# CHARGING.net
KiCad netlist of a schematic drawn in Altium Designer
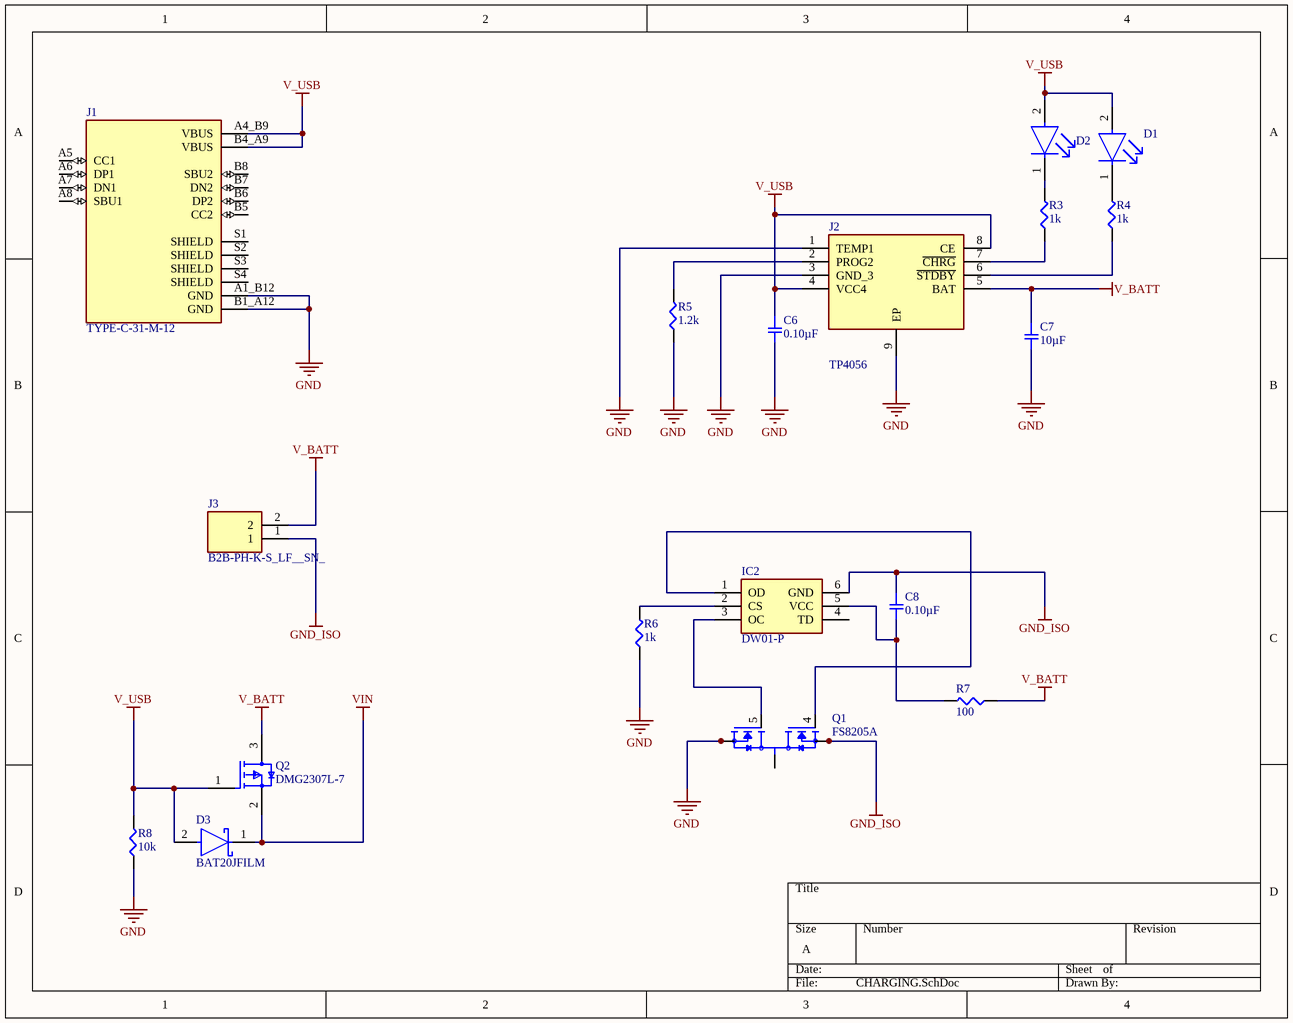
[diagram p0: CHARGING.SchDoc]

(export (version "E")
  (design (tool "Eeschema 10.0.6"))
  (components
    (comp (ref "C6")
      (value "0.10µF")
      (footprint "SMD-0402C")
      (description "CAP CER 0.1UF 16V X7R 0402")
      (fields
        (field (name "DIGI-KEY PART NUMBER") "490-4759-1-ND")
        (field (name "PART NUMBER") "GCM155R71C104KA55D")
      )
      (libsource (lib "capacitor_murata_0402") (part "GCM155R71C104KA55D"))
    )
    (comp (ref "C7")
      (value "10µF")
      (footprint "SMD-0402C")
      (description "CAP CER 10UF 6.3V X5R 0402")
      (fields
        (field (name "DIGI-KEY PART NUMBER") "490-13211-1-ND")
        (field (name "PART NUMBER") "GRJ155R60J106ME11D")
      )
      (libsource (lib "capacitor_murata_0402") (part "GRJ155R60J106ME11D"))
    )
    (comp (ref "C8")
      (value "0.10µF")
      (footprint "SMD-0402C")
      (description "CAP CER 0.1UF 16V X7R 0402")
      (fields
        (field (name "DIGI-KEY PART NUMBER") "490-4759-1-ND")
        (field (name "PART NUMBER") "GCM155R71C104KA55D")
      )
      (libsource (lib "capacitor_murata_0402") (part "GCM155R71C104KA55D"))
    )
    (comp (ref "D1")
      (value "SML-P12VTT86R")
      (footprint "FP-SML-P1-MFG")
      (description "LED RED CLEAR 0402 SMD")
      (fields
        (field (name "OCTOPART") "https://octopart.com/sml-p12vtt86r-rohm-34112315")
        (field (name "MANUFACTURER") "Rohm")
      )
      (libsource (lib "Altium Content Vault") (part "8706943c75ba83719d021d2fdc84c58"))
    )
    (comp (ref "D2")
      (value "APHHS1005CGCK")
      (footprint "FP-APHHS1005CGCK-MFG")
      (description "LED GREEN CLEAR CHIP SMD")
      (libsource (lib "Altium Content Vault") (part "8706943c75ba83719d021d2fdc84c58"))
    )
    (comp (ref "D3")
      (value "BAT20JFILM")
      (footprint "FP-BAT20JFILM-MFG")
      (description "DIODE SCHOTTKY 23V 1A SOD323")
      (libsource (lib "Altium Content Vault") (part "fefb30dabb5d097ae2f038500735429"))
    )
    (comp (ref "IC2")
      (value "DW01-P")
      (footprint "SamacSys:SOT95P280X135-6N")
      (description "Integrated Circuit")
      (libsource (lib "*") (part "DW01-P"))
    )
    (comp (ref "J1")
      (value "TYPE-C-31-M-12")
      (footprint "HRO_TYPE-C-31-M-12")
      (description "USB Connectors 24 Receptacle 1 8.94*7.3mm RoHS")
      (fields (field (name "MF") "HRO Electronics Co., Ltd."))
      (libsource (lib "TYPE-C-31-M-12") (part "TYPE-C-31-M-12"))
    )
    (comp (ref "J2")
      (value "TP4056")
      (footprint "SamacSys:SOIC127P600X175-9N")
      (description "Connector")
      (libsource (lib "SamacSys") (part "TP4056"))
    )
    (comp (ref "J3")
      (value "B2B-PH-K-S_LF__SN_")
      (footprint "SamacSys:SHDR2W50P0X200_1X2_590X450X600P")
      (description "Connector")
      (fields
        (field (name "MANUFACTURER_PART_NUMBER") "B2B-PH-K-S(LF)(SN)")
        (field (name "MOUSER PART NUMBER") "306-B2BPHKSLFSNPP")
      )
      (libsource (lib "*") (part "B2B-PH-K-S_LF__SN_"))
    )
    (comp (ref "Q1")
      (value "FS8205A")
      (footprint "SOP65P640X120-8N")
      (fields (field (name "MF") "Fortune Semiconductor"))
      (libsource (lib "FS8205A (2)") (part "FS8205A"))
    )
    (comp (ref "Q2")
      (value "DMG2307L-7")
      (footprint "FP-SOT23-MFG")
      (description "MOSFET P-CH 30V 2.5A SOT-23")
      (libsource (lib "Altium Content Vault") (part "93d33217dd9b7373daa85f78e0218cc"))
    )
    (comp (ref "R3")
      (value "1k")
      (footprint "SMD-0402-RES")
      (description "RES SMD 1K OHM 5% 1/10W 0402")
      (fields (field (name "PART NUMBER") "ERJ-2GEJ102X") (field (name "DIGI-KEY PART NUMBER") "P1.0KJCT-ND"))
      (libsource (lib "Panasonic_ERJ_0402") (part "ERJ-2GEJ102X"))
    )
    (comp (ref "R4")
      (value "1k")
      (footprint "SMD-0402-RES")
      (description "RES SMD 1K OHM 5% 1/10W 0402")
      (fields (field (name "PART NUMBER") "ERJ-2GEJ102X") (field (name "DIGI-KEY PART NUMBER") "P1.0KJCT-ND"))
      (libsource (lib "Panasonic_ERJ_0402") (part "ERJ-2GEJ102X"))
    )
    (comp (ref "R5")
      (value "1.2k")
      (footprint "SMD-0402-RES")
      (description "RES SMD 1.2K OHM 5% 1/10W 0402")
      (fields (field (name "PART NUMBER") "ERJ-2GEJ122X") (field (name "DIGI-KEY PART NUMBER") "P1.2KJCT-ND"))
      (libsource (lib "Panasonic_ERJ_0402") (part "ERJ-2GEJ122X"))
    )
    (comp (ref "R6")
      (value "1k")
      (footprint "SMD-0402-RES")
      (description "RES SMD 1K OHM 5% 1/10W 0402")
      (fields (field (name "PART NUMBER") "ERJ-2GEJ102X") (field (name "DIGI-KEY PART NUMBER") "P1.0KJCT-ND"))
      (libsource (lib "Panasonic_ERJ_0402") (part "ERJ-2GEJ102X"))
    )
    (comp (ref "R7")
      (value "100")
      (footprint "SMD-0402-RES")
      (description "RES SMD 100 OHM 0.5% 1/16W 0402")
      (fields
        (field (name "PART NUMBER") "ERJ-2RHD1000X")
        (field (name "DIGI-KEY PART NUMBER") "P15983CT-ND")
      )
      (libsource (lib "Panasonic_ERJ_0402") (part "ERJ-2RHD1000X"))
    )
    (comp (ref "R8")
      (value "10k")
      (footprint "SMD-0402-RES")
      (description "RES SMD 10K OHM 5% 1/10W 0402")
      (fields (field (name "PART NUMBER") "ERJ-2GEJ103X") (field (name "DIGI-KEY PART NUMBER") "P10KJCT-ND"))
      (libsource (lib "Panasonic_ERJ_0402") (part "ERJ-2GEJ103X"))
    )
  )
  (nets
    (net (code "1") (name "GND") (class "Default")
      (node (ref "C6") (pin "2") (pinfunction "2_2") (pintype "passive"))
      (node (ref "C7") (pin "2") (pinfunction "2_2") (pintype "passive"))
      (node (ref "J1") (pin "A1_B12") (pinfunction "GND_A1_B12") (pintype "power_in"))
      (node (ref "J1") (pin "B1_A12") (pinfunction "GND_B1_A12") (pintype "power_in"))
      (node (ref "J2") (pin "1") (pinfunction "TEMP1_1") (pintype "passive"))
      (node (ref "J2") (pin "3") (pinfunction "GND_3_3") (pintype "passive"))
      (node (ref "J2") (pin "9") (pinfunction "EP_9") (pintype "passive"))
      (node (ref "Q1") (pin "6") (pinfunction "S2_6") (pintype "passive"))
      (node (ref "Q1") (pin "7") (pinfunction "S2_7") (pintype "passive"))
      (node (ref "R5") (pin "1") (pinfunction "1_1") (pintype "passive"))
      (node (ref "R6") (pin "1") (pinfunction "1_1") (pintype "passive"))
      (node (ref "R8") (pin "1") (pinfunction "1_1") (pintype "passive"))
    )
    (net (code "2") (name "GND_ISO") (class "Default")
      (node (ref "C8") (pin "1") (pinfunction "1_1") (pintype "passive"))
      (node (ref "IC2") (pin "6") (pinfunction "GND_6") (pintype "passive"))
      (node (ref "J3") (pin "1") (pinfunction "1_1") (pintype "passive"))
      (node (ref "Q1") (pin "2") (pinfunction "S1_2") (pintype "passive"))
      (node (ref "Q1") (pin "3") (pinfunction "S1_3") (pintype "passive"))
    )
    (net (code "3") (name "Net-(D1-C)") (class "Default")
      (node (ref "D1") (pin "1") (pinfunction "C_1") (pintype "passive"))
      (node (ref "R4") (pin "2") (pinfunction "2_2") (pintype "passive"))
    )
    (net (code "4") (name "Net-(D2-C)") (class "Default")
      (node (ref "D2") (pin "1") (pinfunction "C_1") (pintype "passive"))
      (node (ref "R3") (pin "2") (pinfunction "2_2") (pintype "passive"))
    )
    (net (code "5") (name "Net-(IC2-CS)") (class "Default")
      (node (ref "IC2") (pin "2") (pinfunction "CS_2") (pintype "passive"))
      (node (ref "R6") (pin "2") (pinfunction "2_2") (pintype "passive"))
    )
    (net (code "6") (name "Net-(IC2-OC)") (class "Default")
      (node (ref "IC2") (pin "3") (pinfunction "OC_3") (pintype "passive"))
      (node (ref "Q1") (pin "5") (pinfunction "G2_5") (pintype "passive"))
    )
    (net (code "7") (name "Net-(IC2-OD)") (class "Default")
      (node (ref "IC2") (pin "1") (pinfunction "OD_1") (pintype "passive"))
      (node (ref "Q1") (pin "4") (pinfunction "G1_4") (pintype "passive"))
    )
    (net (code "8") (name "Net-(IC2-VCC)") (class "Default")
      (node (ref "C8") (pin "2") (pinfunction "2_2") (pintype "passive"))
      (node (ref "IC2") (pin "5") (pinfunction "VCC_5") (pintype "passive"))
      (node (ref "R7") (pin "2") (pinfunction "2_2") (pintype "passive"))
    )
    (net (code "9") (name "Net-(J2-PROG2)") (class "Default")
      (node (ref "J2") (pin "2") (pinfunction "PROG2_2") (pintype "passive"))
      (node (ref "R5") (pin "2") (pinfunction "2_2") (pintype "passive"))
    )
    (net (code "10") (name "Net-(J2-~{CHRG})") (class "Default")
      (node (ref "J2") (pin "7") (pinfunction "~{CHRG}_7") (pintype "passive"))
      (node (ref "R3") (pin "1") (pinfunction "1_1") (pintype "passive"))
    )
    (net (code "11") (name "Net-(J2-~{STDBY})") (class "Default")
      (node (ref "J2") (pin "6") (pinfunction "~{STDBY}_6") (pintype "passive"))
      (node (ref "R4") (pin "1") (pinfunction "1_1") (pintype "passive"))
    )
    (net (code "12") (name "Net-(Q1-D12-Pad1)") (class "Default")
      (node (ref "Q1") (pin "1") (pinfunction "D12_1") (pintype "passive"))
      (node (ref "Q1") (pin "8") (pinfunction "D12_8") (pintype "passive"))
    )
    (net (code "13") (name "VIN") (class "Default")
      (node (ref "D3") (pin "1") (pinfunction "K_1") (pintype "passive"))
      (node (ref "Q2") (pin "2") (pinfunction "S_2") (pintype "passive"))
    )
    (net (code "14") (name "V_BATT") (class "Default")
      (node (ref "C7") (pin "1") (pinfunction "1_1") (pintype "passive"))
      (node (ref "J2") (pin "5") (pinfunction "BAT_5") (pintype "passive"))
      (node (ref "J3") (pin "2") (pinfunction "2_2") (pintype "passive"))
      (node (ref "Q2") (pin "3") (pinfunction "D_3") (pintype "passive"))
      (node (ref "R7") (pin "1") (pinfunction "1_1") (pintype "passive"))
    )
    (net (code "15") (name "V_USB") (class "Default")
      (node (ref "C6") (pin "1") (pinfunction "1_1") (pintype "passive"))
      (node (ref "D1") (pin "2") (pinfunction "A_2") (pintype "passive"))
      (node (ref "D2") (pin "2") (pinfunction "A_2") (pintype "passive"))
      (node (ref "D3") (pin "2") (pinfunction "A_2") (pintype "passive"))
      (node (ref "J1") (pin "A4_B9") (pinfunction "VBUS_A4_B9") (pintype "power_in"))
      (node (ref "J1") (pin "B4_A9") (pinfunction "VBUS_B4_A9") (pintype "power_in"))
      (node (ref "J2") (pin "4") (pinfunction "VCC4_4") (pintype "passive"))
      (node (ref "J2") (pin "8") (pinfunction "CE_8") (pintype "passive"))
      (node (ref "Q2") (pin "1") (pinfunction "G_1") (pintype "passive"))
      (node (ref "R8") (pin "2") (pinfunction "2_2") (pintype "passive"))
    )
    (net (code "16") (name "unconnected-(IC2-TD-Pad4)") (class "Default")
      (node (ref "IC2") (pin "4") (pinfunction "TD_4") (pintype "passive"))
    )
    (net (code "17") (name "unconnected-(J1-CC1-PadA5)") (class "Default")
      (node (ref "J1") (pin "A5") (pinfunction "CC1_A5") (pintype "bidirectional"))
    )
    (net (code "18") (name "unconnected-(J1-CC2-PadB5)") (class "Default")
      (node (ref "J1") (pin "B5") (pinfunction "CC2_B5") (pintype "bidirectional"))
    )
    (net (code "19") (name "unconnected-(J1-DN1-PadA7)") (class "Default")
      (node (ref "J1") (pin "A7") (pinfunction "DN1_A7") (pintype "bidirectional"))
    )
    (net (code "20") (name "unconnected-(J1-DN2-PadB7)") (class "Default")
      (node (ref "J1") (pin "B7") (pinfunction "DN2_B7") (pintype "bidirectional"))
    )
    (net (code "21") (name "unconnected-(J1-DP1-PadA6)") (class "Default")
      (node (ref "J1") (pin "A6") (pinfunction "DP1_A6") (pintype "bidirectional"))
    )
    (net (code "22") (name "unconnected-(J1-DP2-PadB6)") (class "Default")
      (node (ref "J1") (pin "B6") (pinfunction "DP2_B6") (pintype "bidirectional"))
    )
    (net (code "23") (name "unconnected-(J1-SBU1-PadA8)") (class "Default")
      (node (ref "J1") (pin "A8") (pinfunction "SBU1_A8") (pintype "bidirectional"))
    )
    (net (code "24") (name "unconnected-(J1-SBU2-PadB8)") (class "Default")
      (node (ref "J1") (pin "B8") (pinfunction "SBU2_B8") (pintype "bidirectional"))
    )
    (net (code "25") (name "unconnected-(J1-SHIELD-PadS1)") (class "Default")
      (node (ref "J1") (pin "S1") (pinfunction "SHIELD_S1") (pintype "passive"))
    )
    (net (code "26") (name "unconnected-(J1-SHIELD-PadS2)") (class "Default")
      (node (ref "J1") (pin "S2") (pinfunction "SHIELD_S2") (pintype "passive"))
    )
    (net (code "27") (name "unconnected-(J1-SHIELD-PadS3)") (class "Default")
      (node (ref "J1") (pin "S3") (pinfunction "SHIELD_S3") (pintype "passive"))
    )
    (net (code "28") (name "unconnected-(J1-SHIELD-PadS4)") (class "Default")
      (node (ref "J1") (pin "S4") (pinfunction "SHIELD_S4") (pintype "passive"))
    )
  )
)
